# Joystick.net
KiCad netlist of a schematic drawn in EAGLE
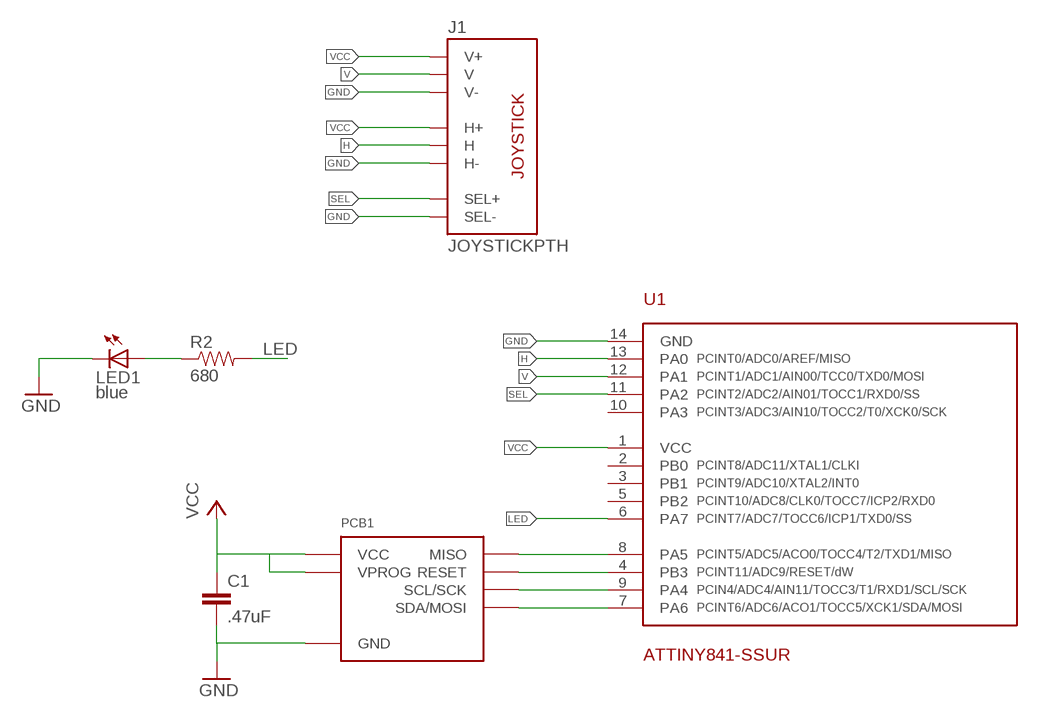
[diagram p0: schematic, sheet 1]

(export (version "E")
  (design (tool "Eeschema 10.0.6"))
  (components
    (comp (ref "C1")
      (value ".47uF")
      (footprint "eagle-import:0805")
      (libsource (lib "eagle-import") (part "CAP0805"))
    )
    (comp (ref "J1")
      (value "JOYSTICKPTH")
      (footprint "eagle-import:JOYSTICK")
      (libsource (lib "eagle-import") (part "JOYSTICKPTH"))
    )
    (comp (ref "LED1")
      (value "blue")
      (footprint "eagle-import:0805-LED")
      (fields (field (name "PARTNUM") "LTST-C171TBKT"))
      (libsource (lib "eagle-import") (part "LED-0805-BLUE"))
    )
    (comp (ref "PCB1")
      (value "MAGDEVICE-V2")
      (footprint "eagle-import:MAGDEVICE-V2")
      (libsource (lib "eagle-import") (part "MAGDEVICE-V2"))
    )
    (comp (ref "R2")
      (value "680")
      (footprint "eagle-import:0805")
      (libsource (lib "eagle-import") (part "RESISTOR0805-RES"))
    )
    (comp (ref "U1")
      (value "ATTINY841-SSUR")
      (footprint "eagle-import:SOIC-14")
      (libsource (lib "eagle-import") (part "ATTINY841"))
    )
  )
  (nets
    (net (code "1") (name "GND") (class "Default")
      (node (ref "C1") (pin "2") (pinfunction "2_2") (pintype "passive"))
      (node (ref "J1") (pin "B2A") (pinfunction "SEL-_B2A") (pintype "bidirectional"))
      (node (ref "J1") (pin "H3") (pinfunction "H-_H3") (pintype "bidirectional"))
      (node (ref "J1") (pin "V3") (pinfunction "V-_V3") (pintype "bidirectional"))
      (node (ref "LED1") (pin "C") (pinfunction "C_C") (pintype "passive"))
      (node (ref "PCB1") (pin "GND") (pinfunction "GND_GND") (pintype "bidirectional"))
      (node (ref "U1") (pin "14") (pinfunction "GND_14") (pintype "bidirectional"))
    )
    (net (code "2") (name "H") (class "Default")
      (node (ref "J1") (pin "H2") (pinfunction "H_H2") (pintype "bidirectional"))
      (node (ref "U1") (pin "13") (pinfunction "PA0_13") (pintype "bidirectional"))
    )
    (net (code "3") (name "LED") (class "Default")
      (node (ref "R2") (pin "2") (pinfunction "2_2") (pintype "passive"))
      (node (ref "U1") (pin "6") (pinfunction "PA7_6") (pintype "bidirectional"))
    )
    (net (code "4") (name "Net-(LED1-PadA)") (class "Default")
      (node (ref "LED1") (pin "A") (pinfunction "A_A") (pintype "passive"))
      (node (ref "R2") (pin "1") (pinfunction "1_1") (pintype "passive"))
    )
    (net (code "5") (name "Net-(PCB1-SCL{slash}SCK)") (class "Default")
      (node (ref "PCB1") (pin "SCL") (pinfunction "SCL/SCK_SCL") (pintype "bidirectional"))
      (node (ref "U1") (pin "9") (pinfunction "PA4_9") (pintype "bidirectional"))
    )
    (net (code "6") (name "Net-(PCB1-SDA{slash}MOSI)") (class "Default")
      (node (ref "PCB1") (pin "SDA") (pinfunction "SDA/MOSI_SDA") (pintype "bidirectional"))
      (node (ref "U1") (pin "7") (pinfunction "PA6_7") (pintype "bidirectional"))
    )
    (net (code "7") (name "Net-(U1-PA5)") (class "Default")
      (node (ref "PCB1") (pin "MISO") (pinfunction "MISO_MISO") (pintype "bidirectional"))
      (node (ref "U1") (pin "8") (pinfunction "PA5_8") (pintype "bidirectional"))
    )
    (net (code "8") (name "Net-(U1-PB3)") (class "Default")
      (node (ref "PCB1") (pin "RESET") (pinfunction "RESET_RESET") (pintype "bidirectional"))
      (node (ref "U1") (pin "4") (pinfunction "PB3_4") (pintype "bidirectional"))
    )
    (net (code "9") (name "SEL") (class "Default")
      (node (ref "J1") (pin "B1A") (pinfunction "SEL+_B1A") (pintype "bidirectional"))
      (node (ref "U1") (pin "11") (pinfunction "PA2_11") (pintype "bidirectional"))
    )
    (net (code "10") (name "V") (class "Default")
      (node (ref "J1") (pin "V2") (pinfunction "V_V2") (pintype "bidirectional"))
      (node (ref "U1") (pin "12") (pinfunction "PA1_12") (pintype "bidirectional"))
    )
    (net (code "11") (name "VCC") (class "Default")
      (node (ref "C1") (pin "1") (pinfunction "1_1") (pintype "passive"))
      (node (ref "J1") (pin "H1") (pinfunction "H+_H1") (pintype "bidirectional"))
      (node (ref "J1") (pin "V1") (pinfunction "V+_V1") (pintype "bidirectional"))
      (node (ref "PCB1") (pin "VCC") (pinfunction "VCC_VCC") (pintype "bidirectional"))
      (node (ref "PCB1") (pin "VPROG") (pinfunction "VPROG_VPROG") (pintype "bidirectional"))
      (node (ref "U1") (pin "1") (pinfunction "VCC_1") (pintype "bidirectional"))
    )
    (net (code "12") (name "unconnected-(U1-PA3-Pad10)") (class "Default")
      (node (ref "U1") (pin "10") (pinfunction "PA3_10") (pintype "bidirectional"))
    )
    (net (code "13") (name "unconnected-(U1-PB0-Pad2)") (class "Default")
      (node (ref "U1") (pin "2") (pinfunction "PB0_2") (pintype "bidirectional"))
    )
    (net (code "14") (name "unconnected-(U1-PB1-Pad3)") (class "Default")
      (node (ref "U1") (pin "3") (pinfunction "PB1_3") (pintype "bidirectional"))
    )
    (net (code "15") (name "unconnected-(U1-PB2-Pad5)") (class "Default")
      (node (ref "U1") (pin "5") (pinfunction "PB2_5") (pintype "bidirectional"))
    )
  )
)
